# Pi_grammer_SPI_ISOLATE.net
KiCad netlist of a schematic drawn in EAGLE
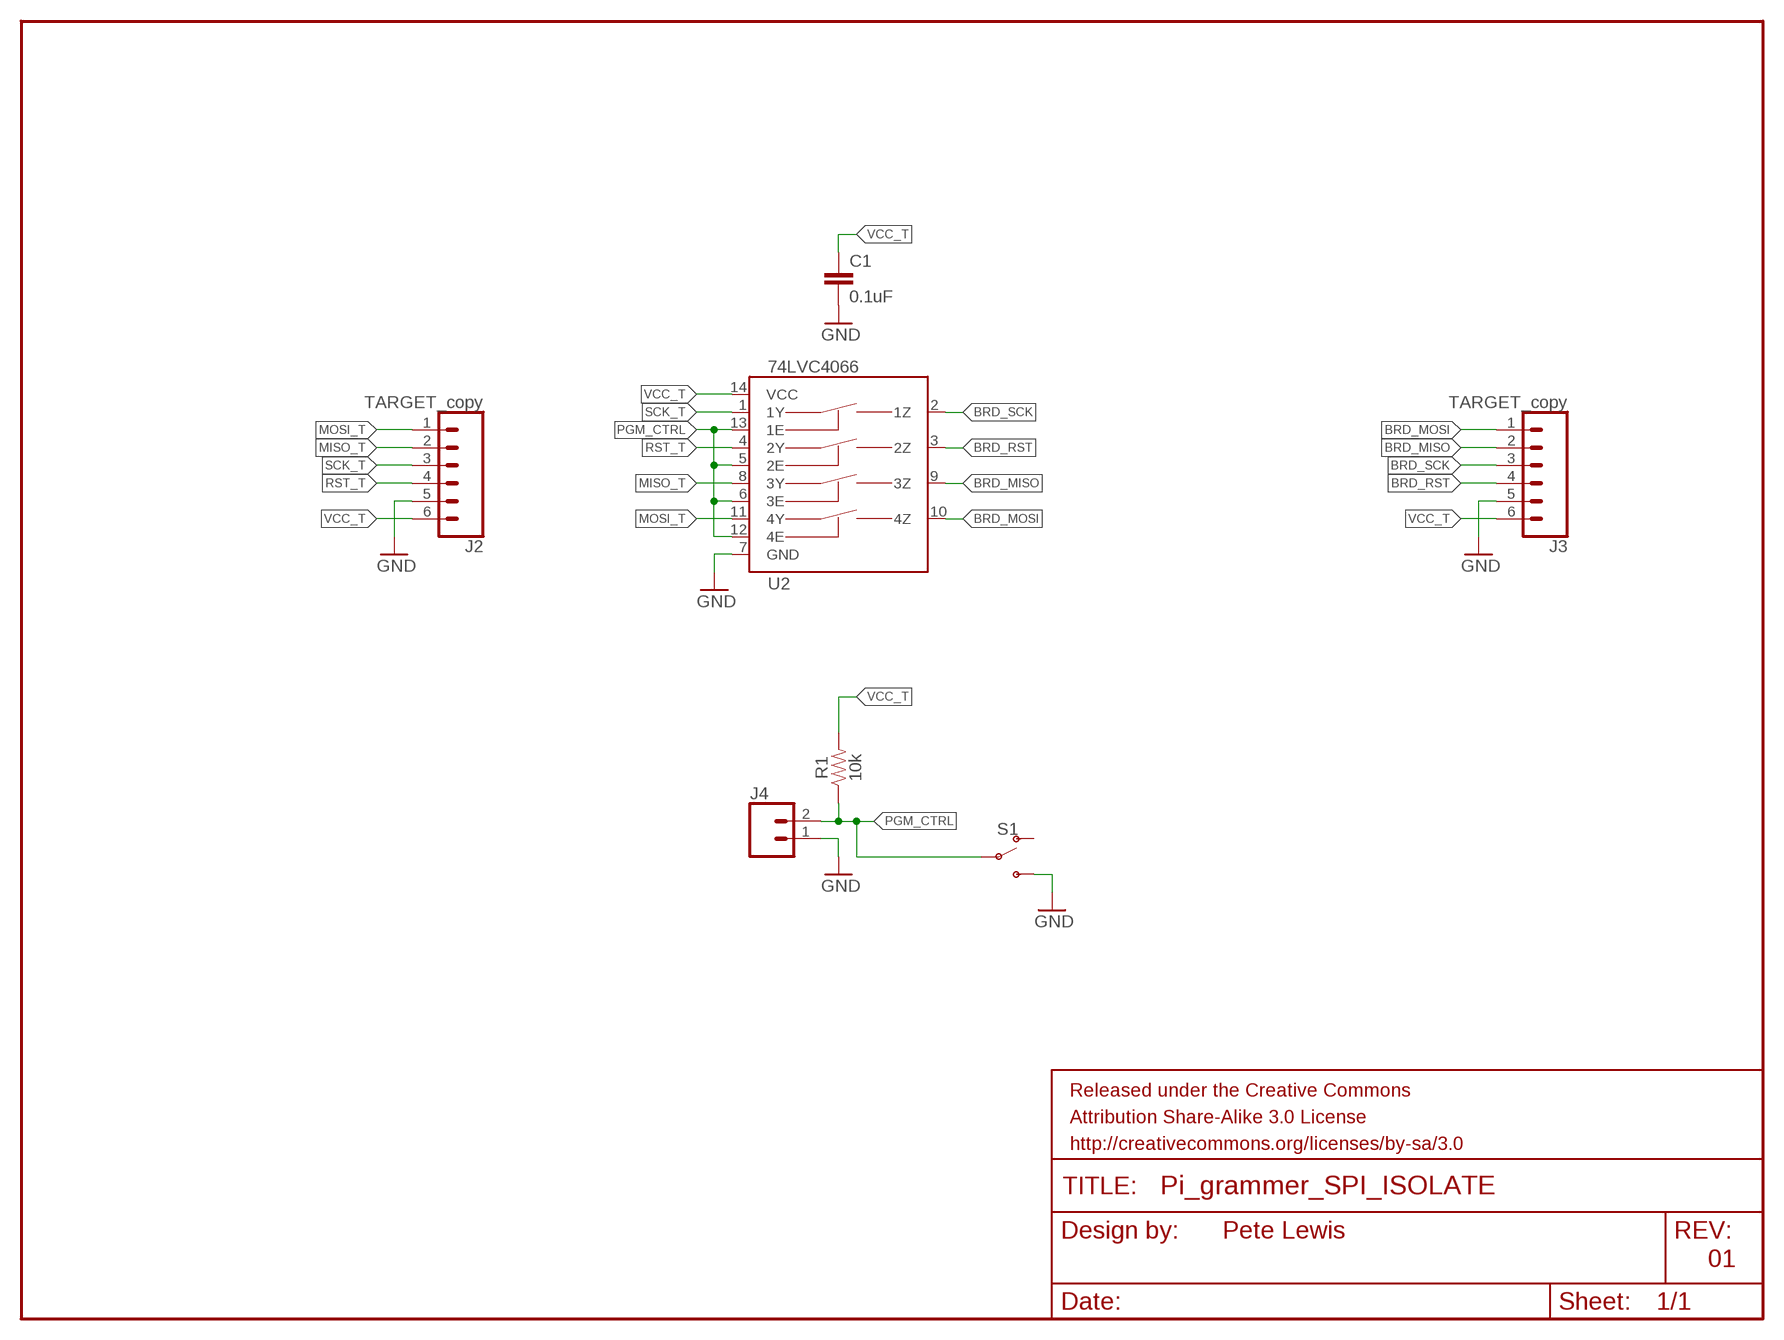
[diagram p0: schematic, sheet 1]

(export (version "E")
  (design (tool "Eeschema 10.0.6"))
  (components
    (comp (ref "C1")
      (value "0.1uF")
      (footprint "eagle-import:0603")
      (libsource (lib "eagle-import") (part "0.1UF-0603-25V-(+80/-20%)"))
    )
    (comp (ref "J2")
      (value "TARGET_copy")
      (footprint "eagle-import:1X06_LOCK")
      (libsource (lib "eagle-import") (part "CONN_06LOCK"))
    )
    (comp (ref "J3")
      (value "TARGET_copy")
      (footprint "eagle-import:1X06_LOCK")
      (libsource (lib "eagle-import") (part "CONN_06LOCK"))
    )
    (comp (ref "J4")
      (value "CONN_02")
      (footprint "eagle-import:1X02")
      (libsource (lib "eagle-import") (part "CONN_02"))
    )
    (comp (ref "R1")
      (value "10k")
      (footprint "eagle-import:0603")
      (libsource (lib "eagle-import") (part "10KOHM-0603-1/10W-1%"))
    )
    (comp (ref "S1")
      (value "SWITCH-SPDT-PTH-11.6X4.0MM-LOCK")
      (footprint "eagle-import:SWITCH_SPDT_PTH_11.6X4.0MM_LOCK")
      (libsource (lib "eagle-import") (part "SWITCH-SPDT-PTH-11.6X4.0MM-LOCK"))
    )
    (comp (ref "U2")
      (value "74LVC4066")
      (footprint "eagle-import:SO14")
      (libsource (lib "eagle-import") (part "74LVC4066_MUX_1{colon}1_X4"))
    )
  )
  (nets
    (net (code "1") (name "BRD_MISO") (class "Default")
      (node (ref "J3") (pin "2") (pinfunction "2_2") (pintype "passive"))
      (node (ref "U2") (pin "9") (pinfunction "3Z_9") (pintype "bidirectional"))
    )
    (net (code "2") (name "BRD_MOSI") (class "Default")
      (node (ref "J3") (pin "1") (pinfunction "1_1") (pintype "passive"))
      (node (ref "U2") (pin "10") (pinfunction "4Z_10") (pintype "bidirectional"))
    )
    (net (code "3") (name "BRD_RST") (class "Default")
      (node (ref "J3") (pin "4") (pinfunction "4_4") (pintype "passive"))
      (node (ref "U2") (pin "3") (pinfunction "2Z_3") (pintype "bidirectional"))
    )
    (net (code "4") (name "BRD_SCK") (class "Default")
      (node (ref "J3") (pin "3") (pinfunction "3_3") (pintype "passive"))
      (node (ref "U2") (pin "2") (pinfunction "1Z_2") (pintype "bidirectional"))
    )
    (net (code "5") (name "GND") (class "Default")
      (node (ref "C1") (pin "2") (pinfunction "2_2") (pintype "passive"))
      (node (ref "J2") (pin "5") (pinfunction "5_5") (pintype "passive"))
      (node (ref "J3") (pin "5") (pinfunction "5_5") (pintype "passive"))
      (node (ref "J4") (pin "1") (pinfunction "1_1") (pintype "passive"))
      (node (ref "S1") (pin "3") (pinfunction "S_3") (pintype "passive"))
      (node (ref "U2") (pin "7") (pinfunction "GND_7") (pintype "bidirectional"))
    )
    (net (code "6") (name "MISO_T") (class "Default")
      (node (ref "J2") (pin "2") (pinfunction "2_2") (pintype "passive"))
      (node (ref "U2") (pin "8") (pinfunction "3Y_8") (pintype "bidirectional"))
    )
    (net (code "7") (name "MOSI_T") (class "Default")
      (node (ref "J2") (pin "1") (pinfunction "1_1") (pintype "passive"))
      (node (ref "U2") (pin "11") (pinfunction "4Y_11") (pintype "bidirectional"))
    )
    (net (code "8") (name "PGM_CTRL") (class "Default")
      (node (ref "J4") (pin "2") (pinfunction "2_2") (pintype "passive"))
      (node (ref "R1") (pin "1") (pinfunction "1_1") (pintype "passive"))
      (node (ref "S1") (pin "2") (pinfunction "P_2") (pintype "passive"))
      (node (ref "U2") (pin "12") (pinfunction "4E_12") (pintype "bidirectional"))
      (node (ref "U2") (pin "13") (pinfunction "1E_13") (pintype "bidirectional"))
      (node (ref "U2") (pin "5") (pinfunction "2E_5") (pintype "bidirectional"))
      (node (ref "U2") (pin "6") (pinfunction "3E_6") (pintype "bidirectional"))
    )
    (net (code "9") (name "RST_T") (class "Default")
      (node (ref "J2") (pin "4") (pinfunction "4_4") (pintype "passive"))
      (node (ref "U2") (pin "4") (pinfunction "2Y_4") (pintype "bidirectional"))
    )
    (net (code "10") (name "SCK_T") (class "Default")
      (node (ref "J2") (pin "3") (pinfunction "3_3") (pintype "passive"))
      (node (ref "U2") (pin "1") (pinfunction "1Y_1") (pintype "bidirectional"))
    )
    (net (code "11") (name "VCC_T") (class "Default")
      (node (ref "C1") (pin "1") (pinfunction "1_1") (pintype "passive"))
      (node (ref "J2") (pin "6") (pinfunction "6_6") (pintype "passive"))
      (node (ref "J3") (pin "6") (pinfunction "6_6") (pintype "passive"))
      (node (ref "R1") (pin "2") (pinfunction "2_2") (pintype "passive"))
      (node (ref "U2") (pin "14") (pinfunction "VCC_14") (pintype "bidirectional"))
    )
    (net (code "12") (name "unconnected-(S1-O-Pad1)") (class "Default")
      (node (ref "S1") (pin "1") (pinfunction "O_1") (pintype "passive"))
    )
  )
)
